# RasPiTimePowerSW_basic.net
KiCad netlist of a schematic drawn in EAGLE
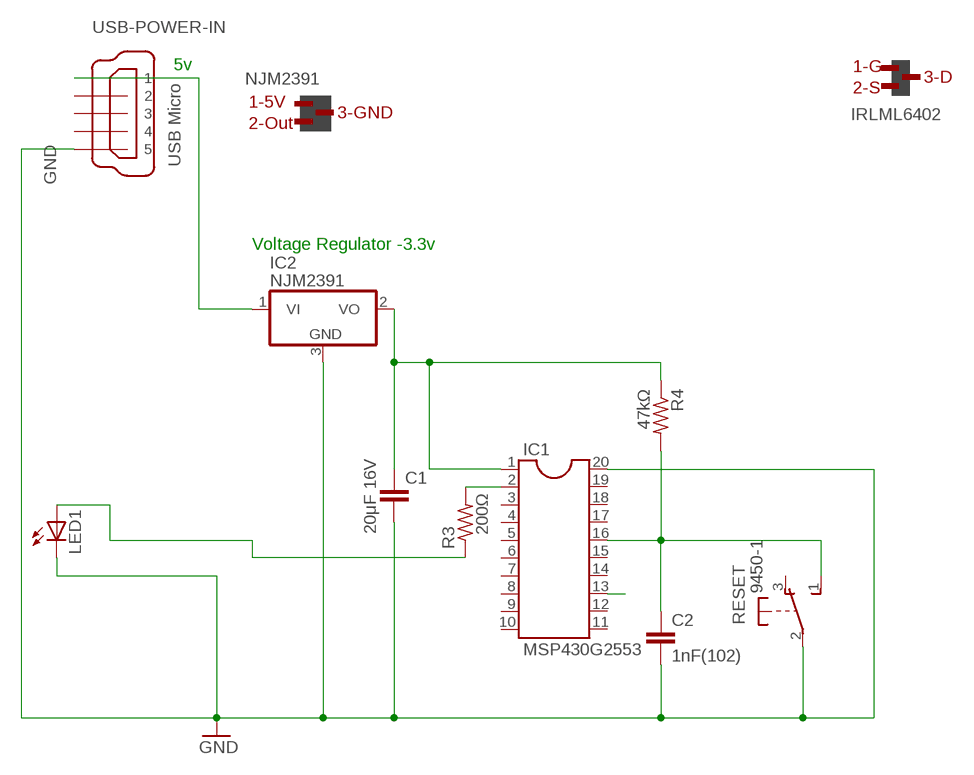
[diagram p0: schematic, sheet 1]

(export (version "E")
  (design (tool "Eeschema 10.0.6"))
  (components
    (comp (ref "C1")
      (value "20μF 16V")
      (footprint "eagle-import:C075-042X103")
      (libsource (lib "eagle-import") (part "C-EU075-042X103"))
    )
    (comp (ref "C2")
      (value "1nF(102)")
      (footprint "eagle-import:C025-024X044")
      (libsource (lib "eagle-import") (part "C-EU025-024X044"))
    )
    (comp (ref "IC1")
      (value "MSP430G2553")
      (footprint "eagle-import:SOCKET-20")
      (libsource (lib "eagle-import") (part "DIL20S"))
    )
    (comp (ref "IC2")
      (value "NJM2391")
      (footprint "eagle-import:TO252")
      (libsource (lib "eagle-import") (part "78DT05"))
    )
    (comp (ref "LED1")
      (value "TLLG4400")
      (footprint "eagle-import:LED3MM")
      (fields (field (name "MF") "VISHAY SEMICONDUCTOR"))
      (libsource (lib "eagle-import") (part "TLLG4400"))
    )
    (comp (ref "R3")
      (value "R-US_MELF0102W")
      (footprint "eagle-import:MINI_MELF-0102W")
      (fields (field (name "R") "200Ω"))
      (libsource (lib "eagle-import") (part "R-US_MELF0102W"))
    )
    (comp (ref "R4")
      (value "47kΩ")
      (footprint "eagle-import:MINI_MELF-0102W")
      (libsource (lib "eagle-import") (part "R-US_MELF0102W"))
    )
    (comp (ref "RESET")
      (value "9450-1")
      (footprint "eagle-import:9450-1")
      (libsource (lib "eagle-import") (part "9450-1"))
    )
    (comp (ref "USB-POWER-IN")
      (value "USB Micro")
      (footprint "eagle-import:32005-400")
      (libsource (lib "eagle-import") (part "MINI-USB_SHIELD5P4-32005-400"))
    )
  )
  (nets
    (net (code "1") (name "GND") (class "Default")
      (node (ref "C1") (pin "2") (pinfunction "2_2") (pintype "passive"))
      (node (ref "C2") (pin "2") (pinfunction "2_2") (pintype "passive"))
      (node (ref "IC1") (pin "20") (pinfunction "20_20") (pintype "passive"))
      (node (ref "IC2") (pin "3") (pinfunction "GND_3") (pintype "passive"))
      (node (ref "LED1") (pin "K") (pinfunction "C_K") (pintype "passive"))
      (node (ref "RESET") (pin "2") (pinfunction "P_2") (pintype "passive"))
      (node (ref "USB-POWER-IN") (pin "5") (pinfunction "5_5") (pintype "passive"))
    )
    (net (code "2") (name "Net-(IC1-Pad2)") (class "Default")
      (node (ref "IC1") (pin "2") (pinfunction "2_2") (pintype "passive"))
      (node (ref "R3") (pin "2") (pinfunction "2_2") (pintype "passive"))
    )
    (net (code "3") (name "Net-(IC2-VI)") (class "Default")
      (node (ref "IC2") (pin "1") (pinfunction "VI_1") (pintype "input"))
      (node (ref "USB-POWER-IN") (pin "1") (pinfunction "1_1") (pintype "passive"))
    )
    (net (code "4") (name "Net-(IC2-VO)") (class "Default")
      (node (ref "C1") (pin "1") (pinfunction "1_1") (pintype "passive"))
      (node (ref "IC1") (pin "1") (pinfunction "1_1") (pintype "passive"))
      (node (ref "IC2") (pin "2") (pinfunction "VO_2") (pintype "passive"))
      (node (ref "R4") (pin "1") (pinfunction "1_1") (pintype "passive"))
    )
    (net (code "5") (name "Net-(LED1-PadA)") (class "Default")
      (node (ref "LED1") (pin "A") (pinfunction "A_A") (pintype "passive"))
      (node (ref "R3") (pin "1") (pinfunction "1_1") (pintype "passive"))
    )
    (net (code "6") (name "Net-(RESET-S)") (class "Default")
      (node (ref "C2") (pin "1") (pinfunction "1_1") (pintype "passive"))
      (node (ref "IC1") (pin "16") (pinfunction "16_16") (pintype "passive"))
      (node (ref "R4") (pin "2") (pinfunction "2_2") (pintype "passive"))
      (node (ref "RESET") (pin "1") (pinfunction "S_1") (pintype "passive"))
    )
    (net (code "7") (name "unconnected-(IC1-Pad3)") (class "Default")
      (node (ref "IC1") (pin "3") (pinfunction "3_3") (pintype "passive"))
    )
    (net (code "8") (name "unconnected-(IC1-Pad4)") (class "Default")
      (node (ref "IC1") (pin "4") (pinfunction "4_4") (pintype "passive"))
    )
    (net (code "9") (name "unconnected-(IC1-Pad5)") (class "Default")
      (node (ref "IC1") (pin "5") (pinfunction "5_5") (pintype "passive"))
    )
    (net (code "10") (name "unconnected-(IC1-Pad6)") (class "Default")
      (node (ref "IC1") (pin "6") (pinfunction "6_6") (pintype "passive"))
    )
    (net (code "11") (name "unconnected-(IC1-Pad7)") (class "Default")
      (node (ref "IC1") (pin "7") (pinfunction "7_7") (pintype "passive"))
    )
    (net (code "12") (name "unconnected-(IC1-Pad8)") (class "Default")
      (node (ref "IC1") (pin "8") (pinfunction "8_8") (pintype "passive"))
    )
    (net (code "13") (name "unconnected-(IC1-Pad9)") (class "Default")
      (node (ref "IC1") (pin "9") (pinfunction "9_9") (pintype "passive"))
    )
    (net (code "14") (name "unconnected-(IC1-Pad10)") (class "Default")
      (node (ref "IC1") (pin "10") (pinfunction "10_10") (pintype "passive"))
    )
    (net (code "15") (name "unconnected-(IC1-Pad11)") (class "Default")
      (node (ref "IC1") (pin "11") (pinfunction "11_11") (pintype "passive"))
    )
    (net (code "16") (name "unconnected-(IC1-Pad12)") (class "Default")
      (node (ref "IC1") (pin "12") (pinfunction "12_12") (pintype "passive"))
    )
    (net (code "17") (name "unconnected-(IC1-Pad13)") (class "Default")
      (node (ref "IC1") (pin "13") (pinfunction "13_13") (pintype "passive"))
    )
    (net (code "18") (name "unconnected-(IC1-Pad14)") (class "Default")
      (node (ref "IC1") (pin "14") (pinfunction "14_14") (pintype "passive"))
    )
    (net (code "19") (name "unconnected-(IC1-Pad15)") (class "Default")
      (node (ref "IC1") (pin "15") (pinfunction "15_15") (pintype "passive"))
    )
    (net (code "20") (name "unconnected-(IC1-Pad17)") (class "Default")
      (node (ref "IC1") (pin "17") (pinfunction "17_17") (pintype "passive"))
    )
    (net (code "21") (name "unconnected-(IC1-Pad18)") (class "Default")
      (node (ref "IC1") (pin "18") (pinfunction "18_18") (pintype "passive"))
    )
    (net (code "22") (name "unconnected-(IC1-Pad19)") (class "Default")
      (node (ref "IC1") (pin "19") (pinfunction "19_19") (pintype "passive"))
    )
    (net (code "23") (name "unconnected-(RESET-O-Pad3)") (class "Default")
      (node (ref "RESET") (pin "3") (pinfunction "O_3") (pintype "passive"))
    )
    (net (code "24") (name "unconnected-(USB-POWER-IN-Pad2)") (class "Default")
      (node (ref "USB-POWER-IN") (pin "2") (pinfunction "2_2") (pintype "passive"))
    )
    (net (code "25") (name "unconnected-(USB-POWER-IN-Pad3)") (class "Default")
      (node (ref "USB-POWER-IN") (pin "3") (pinfunction "3_3") (pintype "passive"))
    )
    (net (code "26") (name "unconnected-(USB-POWER-IN-Pad4)") (class "Default")
      (node (ref "USB-POWER-IN") (pin "4") (pinfunction "4_4") (pintype "passive"))
    )
  )
)
